# IPM_Schematic.net
KiCad netlist of a schematic drawn in Altium Designer
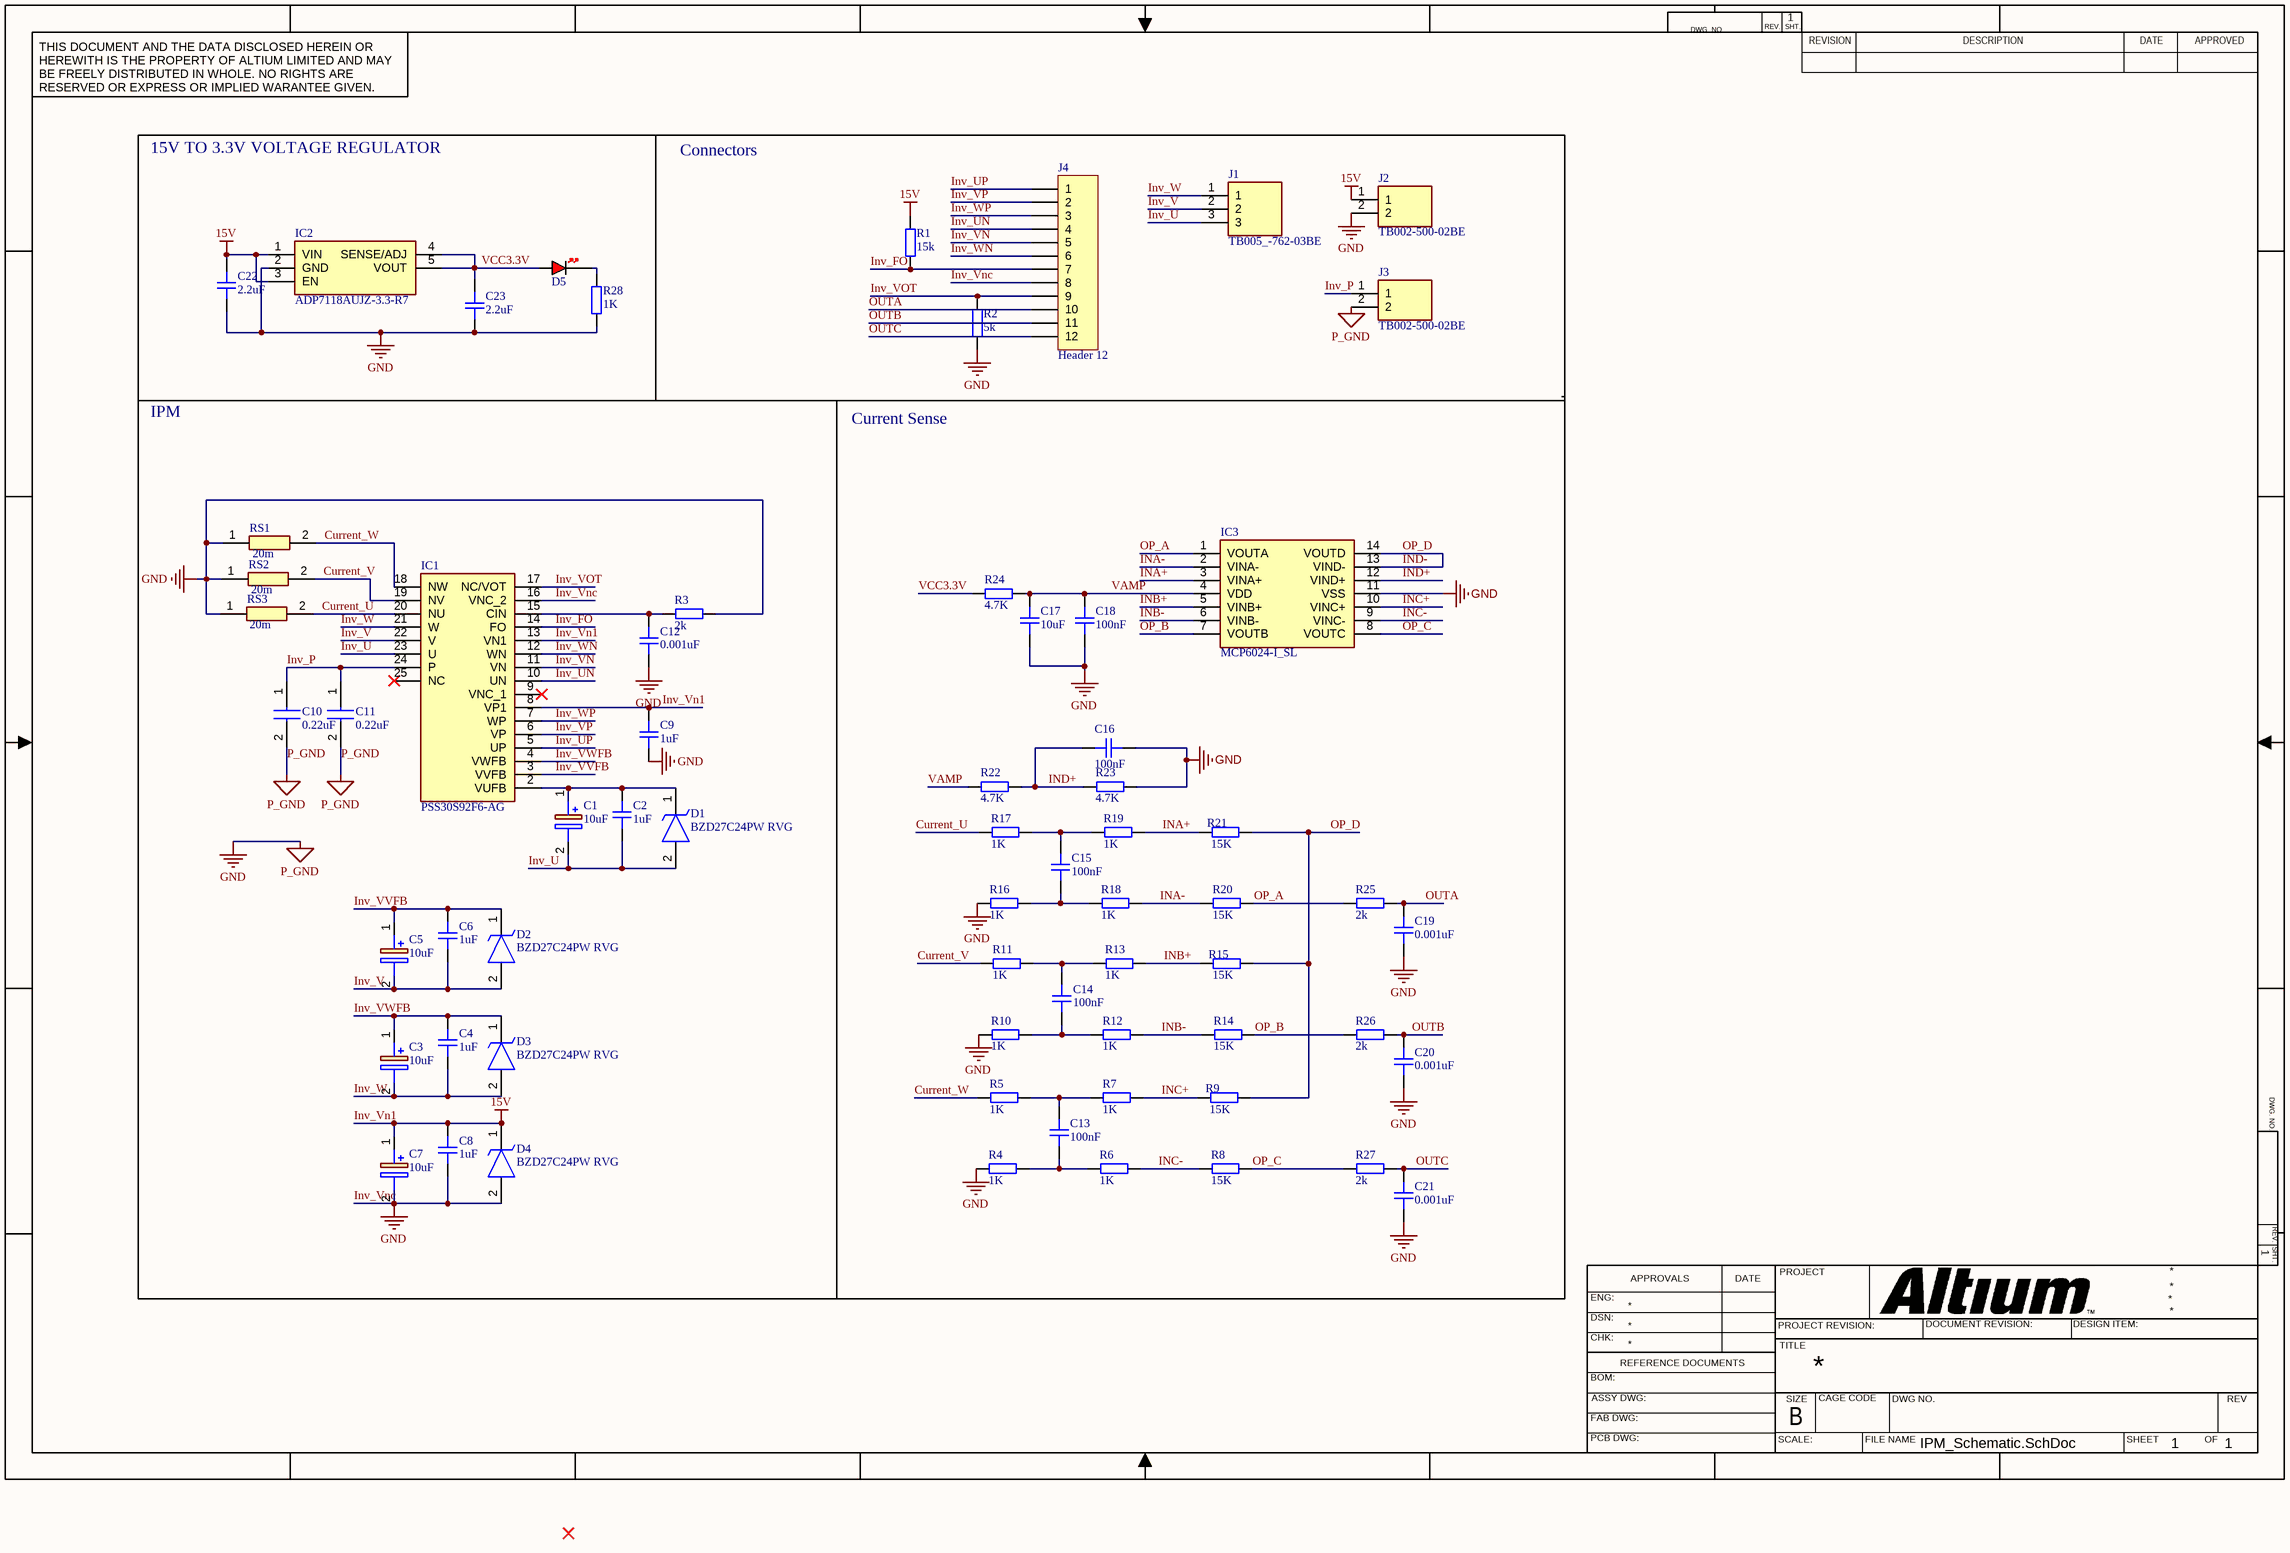
[diagram p0: IPM_Schematic.SchDoc]

(export (version "E")
  (design (tool "Eeschema 10.0.6"))
  (components
    (comp (ref "C1")
      (value "10uF")
      (footprint "SamacSys:EEE1AA220WR")
      (description "Capacitor Polarised")
      (fields
        (field (name "MANUFACTURER_PART_NUMBER") "EEE-FTH100UAR")
        (field (name "MOUSER PART NUMBER") "667-EEE-FTH100UAR")
      )
      (libsource (lib "*") (part "EEE-FTH100UAR"))
    )
    (comp (ref "C2")
      (value "1uF")
      (footprint "CAP_1206")
      (description "Capacitor SMD 1206 50V")
      (libsource (lib "Schematic-Lib-PhilsLab") (part "CAP_1206_50V"))
    )
    (comp (ref "C3")
      (value "10uF")
      (footprint "SamacSys:EEE1AA220WR")
      (description "Capacitor Polarised")
      (fields
        (field (name "MANUFACTURER_PART_NUMBER") "EEE-FTH100UAR")
        (field (name "MOUSER PART NUMBER") "667-EEE-FTH100UAR")
      )
      (libsource (lib "*") (part "EEE-FTH100UAR"))
    )
    (comp (ref "C4")
      (value "1uF")
      (footprint "CAP_1206")
      (description "Capacitor SMD 1206 50V")
      (libsource (lib "Schematic-Lib-PhilsLab") (part "CAP_1206_50V"))
    )
    (comp (ref "C5")
      (value "10uF")
      (footprint "SamacSys:EEE1AA220WR")
      (description "Capacitor Polarised")
      (fields
        (field (name "MANUFACTURER_PART_NUMBER") "EEE-FTH100UAR")
        (field (name "MOUSER PART NUMBER") "667-EEE-FTH100UAR")
      )
      (libsource (lib "*") (part "EEE-FTH100UAR"))
    )
    (comp (ref "C6")
      (value "1uF")
      (footprint "CAP_1206")
      (description "Capacitor SMD 1206 50V")
      (libsource (lib "Schematic-Lib-PhilsLab") (part "CAP_1206_50V"))
    )
    (comp (ref "C7")
      (value "10uF")
      (footprint "SamacSys:EEE1AA220WR")
      (description "Capacitor Polarised")
      (fields
        (field (name "MANUFACTURER_PART_NUMBER") "EEE-FTH100UAR")
        (field (name "MOUSER PART NUMBER") "667-EEE-FTH100UAR")
      )
      (libsource (lib "*") (part "EEE-FTH100UAR"))
    )
    (comp (ref "C8")
      (value "1uF")
      (footprint "CAP_1206")
      (description "Capacitor SMD 1206 50V")
      (libsource (lib "Schematic-Lib-PhilsLab") (part "CAP_1206_50V"))
    )
    (comp (ref "C9")
      (value "1uF")
      (footprint "CAP_1206")
      (description "Capacitor SMD 1206 50V")
      (libsource (lib "Schematic-Lib-PhilsLab") (part "CAP_1206_50V"))
    )
    (comp (ref "C10")
      (value "0.22uF")
      (footprint "SamacSys:CAPC5750X450N")
      (description "Capacitor")
      (fields
        (field (name "MANUFACTURER_PART_NUMBER") "2220Y1K20224KXTWS3")
        (field (name "MOUSER PART NUMBER") "843-2220Y1K20224KXTW")
      )
      (libsource (lib "*") (part "2220Y1K20224KXTWS3"))
    )
    (comp (ref "C11")
      (value "0.22uF")
      (footprint "SamacSys:CAPC5750X450N")
      (description "Capacitor")
      (fields
        (field (name "MANUFACTURER_PART_NUMBER") "2220Y1K20224KXTWS3")
        (field (name "MOUSER PART NUMBER") "843-2220Y1K20224KXTW")
      )
      (libsource (lib "*") (part "2220Y1K20224KXTWS3"))
    )
    (comp (ref "C12")
      (value "0.001uF")
      (footprint "CAP_0805")
      (description "Capacitor SMD 0805 25V")
      (libsource (lib "Schematic-Lib-PhilsLab") (part "CAP_0805_25V"))
    )
    (comp (ref "C13")
      (value "100nF")
      (footprint "CAP_0603")
      (description "Capacitor SMD 0603 50V")
      (libsource (lib "Schematic-Lib-PhilsLab") (part "CAP_0603_50V"))
    )
    (comp (ref "C14")
      (value "100nF")
      (footprint "CAP_0603")
      (description "Capacitor SMD 0603 50V")
      (libsource (lib "Schematic-Lib-PhilsLab") (part "CAP_0603_50V"))
    )
    (comp (ref "C15")
      (value "100nF")
      (footprint "CAP_0603")
      (description "Capacitor SMD 0603 50V")
      (libsource (lib "Schematic-Lib-PhilsLab") (part "CAP_0603_50V"))
    )
    (comp (ref "C16")
      (value "100nF")
      (footprint "CAP_0603")
      (description "Capacitor SMD 0603 50V")
      (libsource (lib "Schematic-Lib-PhilsLab") (part "CAP_0603_50V"))
    )
    (comp (ref "C17")
      (value "10uF")
      (footprint "CAP_0603")
      (description "Capacitor SMD 0603 50V")
      (libsource (lib "Schematic-Lib-PhilsLab") (part "CAP_0603_50V"))
    )
    (comp (ref "C18")
      (value "100nF")
      (footprint "CAP_0603")
      (description "Capacitor SMD 0603 50V")
      (libsource (lib "Schematic-Lib-PhilsLab") (part "CAP_0603_50V"))
    )
    (comp (ref "C19")
      (value "0.001uF")
      (footprint "CAP_0805")
      (description "Capacitor SMD 0805 25V")
      (libsource (lib "Schematic-Lib-PhilsLab") (part "CAP_0805_25V"))
    )
    (comp (ref "C20")
      (value "0.001uF")
      (footprint "CAP_0805")
      (description "Capacitor SMD 0805 25V")
      (libsource (lib "Schematic-Lib-PhilsLab") (part "CAP_0805_25V"))
    )
    (comp (ref "C21")
      (value "0.001uF")
      (footprint "CAP_0805")
      (description "Capacitor SMD 0805 25V")
      (libsource (lib "Schematic-Lib-PhilsLab") (part "CAP_0805_25V"))
    )
    (comp (ref "C22")
      (value "2.2uF")
      (footprint "CAP_0603")
      (description "Capacitor SMD 0603 50V")
      (libsource (lib "Schematic-Lib-PhilsLab") (part "CAP_0603_50V"))
    )
    (comp (ref "C23")
      (value "2.2uF")
      (footprint "CAP_0603")
      (description "Capacitor SMD 0603 50V")
      (libsource (lib "Schematic-Lib-PhilsLab") (part "CAP_0603_50V"))
    )
    (comp (ref "D1")
      (value "BZD27C24PW RVG")
      (footprint "SamacSys:SODFL3718X140N")
      (description "TVS Diode (Uni-directional)")
      (fields
        (field (name "MANUFACTURER_PART_NUMBER") "SJD12A28L01")
        (field (name "MOUSER PART NUMBER") "603-SJD12A28L01")
      )
      (libsource (lib "*") (part "SJD12A28L01"))
    )
    (comp (ref "D2")
      (value "BZD27C24PW RVG")
      (footprint "SamacSys:SODFL3718X140N")
      (description "TVS Diode (Uni-directional)")
      (fields
        (field (name "MANUFACTURER_PART_NUMBER") "SJD12A28L01")
        (field (name "MOUSER PART NUMBER") "603-SJD12A28L01")
      )
      (libsource (lib "*") (part "SJD12A28L01"))
    )
    (comp (ref "D3")
      (value "BZD27C24PW RVG")
      (footprint "SamacSys:SODFL3718X140N")
      (description "TVS Diode (Uni-directional)")
      (fields
        (field (name "MANUFACTURER_PART_NUMBER") "SJD12A28L01")
        (field (name "MOUSER PART NUMBER") "603-SJD12A28L01")
      )
      (libsource (lib "*") (part "SJD12A28L01"))
    )
    (comp (ref "D4")
      (value "BZD27C24PW RVG")
      (footprint "SamacSys:SODFL3718X140N")
      (description "TVS Diode (Uni-directional)")
      (fields
        (field (name "MANUFACTURER_PART_NUMBER") "SJD12A28L01")
        (field (name "MOUSER PART NUMBER") "603-SJD12A28L01")
      )
      (libsource (lib "*") (part "SJD12A28L01"))
    )
    (comp (ref "D5")
      (value "RED")
      (footprint "LED_0402_RED")
      (description "LED 0402 RED SMD")
      (libsource (lib "Schematic-Lib-PhilsLab") (part "LED_0402_RED"))
    )
    (comp (ref "IC1")
      (value "PSS30S92F6-AG")
      (footprint "SamacSys:PSS30S92F6AG")
      (description "Integrated Circuit")
      (fields (field (name "MOUSER PART NUMBER") "917-PSS30S92F6-AG"))
      (libsource (lib "*") (part "PSS30S92F6-AG"))
    )
    (comp (ref "IC2")
      (value "ADP7118AUJZ-3.3-R7")
      (footprint "SamacSys:SOT95P280X100-5N")
      (description "Integrated Circuit")
      (fields (field (name "MOUSER PART NUMBER") "584-ADP7118AUJZ3.3R7"))
      (libsource (lib "*") (part "ADP7118AUJZ-3.3-R7"))
    )
    (comp (ref "IC3")
      (value "MCP6024-I_SL")
      (footprint "SamacSys:SOIC127P600X175-14N")
      (description "Integrated Circuit")
      (fields
        (field (name "MANUFACTURER_PART_NUMBER") "MCP6024-I/SL")
        (field (name "MOUSER PART NUMBER") "579-MCP6024-I/SL")
      )
      (libsource (lib "*") (part "MCP6024-I_SL"))
    )
    (comp (ref "J1")
      (value "TB005_-762-03BE")
      (footprint "CUI_TB005 -762-03BE")
      (description "3 Position Wire to Board Terminal Block Horizontal with Board 0.300 (7.62mm) Through Hole")
      (fields (field (name "MF") "CUI") (field (name "MP") "TB005 -762-03BE"))
      (libsource (lib "TB005_-762-03BE") (part "TB005_-762-03BE"))
    )
    (comp (ref "J2")
      (value "TB002-500-02BE")
      (footprint "SamacSys:TB00250002BE")
      (description "Connector")
      (fields (field (name "MOUSER PART NUMBER") "490-TB002-500-02BE"))
      (libsource (lib "*") (part "TB002-500-02BE"))
    )
    (comp (ref "J3")
      (value "TB002-500-02BE")
      (footprint "SamacSys:TB00250002BE")
      (description "Connector")
      (fields (field (name "MOUSER PART NUMBER") "490-TB002-500-02BE"))
      (libsource (lib "*") (part "TB002-500-02BE"))
    )
    (comp (ref "J4")
      (value "Header 12")
      (footprint "HDR1X12")
      (description "Header, 12-Pin")
      (fields (field (name "PUBLISHER") "Altium Limited"))
      (libsource (lib "Miscellaneous Connectors") (part "Header 12"))
    )
    (comp (ref "R1")
      (value "15k")
      (footprint "RES_0603")
      (description "Resistor SMD 0603")
      (libsource (lib "Schematic-Lib-PhilsLab") (part "RES_0603"))
    )
    (comp (ref "R2")
      (value "5k")
      (footprint "RES_0603")
      (description "Resistor SMD 0603")
      (libsource (lib "Schematic-Lib-PhilsLab") (part "RES_0603"))
    )
    (comp (ref "R3")
      (value "2k")
      (footprint "RES_0805")
      (description "Resistor SMD 0805")
      (libsource (lib "Schematic-Lib-PhilsLab") (part "RES_0805"))
    )
    (comp (ref "R4")
      (value "1K")
      (footprint "RES_0603")
      (description "Resistor SMD 0603")
      (libsource (lib "Schematic-Lib-PhilsLab") (part "RES_0603"))
    )
    (comp (ref "R5")
      (value "1K")
      (footprint "RES_0603")
      (description "Resistor SMD 0603")
      (libsource (lib "Schematic-Lib-PhilsLab") (part "RES_0603"))
    )
    (comp (ref "R6")
      (value "1K")
      (footprint "RES_0603")
      (description "Resistor SMD 0603")
      (libsource (lib "Schematic-Lib-PhilsLab") (part "RES_0603"))
    )
    (comp (ref "R7")
      (value "1K")
      (footprint "RES_0603")
      (description "Resistor SMD 0603")
      (libsource (lib "Schematic-Lib-PhilsLab") (part "RES_0603"))
    )
    (comp (ref "R8")
      (value "15K")
      (footprint "RES_0603")
      (description "Resistor SMD 0603")
      (libsource (lib "Schematic-Lib-PhilsLab") (part "RES_0603"))
    )
    (comp (ref "R9")
      (value "15K")
      (footprint "RES_0603")
      (description "Resistor SMD 0603")
      (libsource (lib "Schematic-Lib-PhilsLab") (part "RES_0603"))
    )
    (comp (ref "R10")
      (value "1K")
      (footprint "RES_0603")
      (description "Resistor SMD 0603")
      (libsource (lib "Schematic-Lib-PhilsLab") (part "RES_0603"))
    )
    (comp (ref "R11")
      (value "1K")
      (footprint "RES_0603")
      (description "Resistor SMD 0603")
      (libsource (lib "Schematic-Lib-PhilsLab") (part "RES_0603"))
    )
    (comp (ref "R12")
      (value "1K")
      (footprint "RES_0603")
      (description "Resistor SMD 0603")
      (libsource (lib "Schematic-Lib-PhilsLab") (part "RES_0603"))
    )
    (comp (ref "R13")
      (value "1K")
      (footprint "RES_0603")
      (description "Resistor SMD 0603")
      (libsource (lib "Schematic-Lib-PhilsLab") (part "RES_0603"))
    )
    (comp (ref "R14")
      (value "15K")
      (footprint "RES_0603")
      (description "Resistor SMD 0603")
      (libsource (lib "Schematic-Lib-PhilsLab") (part "RES_0603"))
    )
    (comp (ref "R15")
      (value "15K")
      (footprint "RES_0603")
      (description "Resistor SMD 0603")
      (libsource (lib "Schematic-Lib-PhilsLab") (part "RES_0603"))
    )
    (comp (ref "R16")
      (value "1K")
      (footprint "RES_0603")
      (description "Resistor SMD 0603")
      (libsource (lib "Schematic-Lib-PhilsLab") (part "RES_0603"))
    )
    (comp (ref "R17")
      (value "1K")
      (footprint "RES_0603")
      (description "Resistor SMD 0603")
      (libsource (lib "Schematic-Lib-PhilsLab") (part "RES_0603"))
    )
    (comp (ref "R18")
      (value "1K")
      (footprint "RES_0603")
      (description "Resistor SMD 0603")
      (libsource (lib "Schematic-Lib-PhilsLab") (part "RES_0603"))
    )
    (comp (ref "R19")
      (value "1K")
      (footprint "RES_0603")
      (description "Resistor SMD 0603")
      (libsource (lib "Schematic-Lib-PhilsLab") (part "RES_0603"))
    )
    (comp (ref "R20")
      (value "15K")
      (footprint "RES_0603")
      (description "Resistor SMD 0603")
      (libsource (lib "Schematic-Lib-PhilsLab") (part "RES_0603"))
    )
    (comp (ref "R21")
      (value "15K")
      (footprint "RES_0603")
      (description "Resistor SMD 0603")
      (libsource (lib "Schematic-Lib-PhilsLab") (part "RES_0603"))
    )
    (comp (ref "R22")
      (value "4.7K")
      (footprint "RES_0603")
      (description "Resistor SMD 0603")
      (libsource (lib "Schematic-Lib-PhilsLab") (part "RES_0603"))
    )
    (comp (ref "R23")
      (value "4.7K")
      (footprint "RES_0603")
      (description "Resistor SMD 0603")
      (libsource (lib "Schematic-Lib-PhilsLab") (part "RES_0603"))
    )
    (comp (ref "R24")
      (value "4.7K")
      (footprint "RES_0603")
      (description "Resistor SMD 0603")
      (libsource (lib "Schematic-Lib-PhilsLab") (part "RES_0603"))
    )
    (comp (ref "R25")
      (value "2k")
      (footprint "RES_0805")
      (description "Resistor SMD 0805")
      (libsource (lib "Schematic-Lib-PhilsLab") (part "RES_0805"))
    )
    (comp (ref "R26")
      (value "2k")
      (footprint "RES_0805")
      (description "Resistor SMD 0805")
      (libsource (lib "Schematic-Lib-PhilsLab") (part "RES_0805"))
    )
    (comp (ref "R27")
      (value "2k")
      (footprint "RES_0805")
      (description "Resistor SMD 0805")
      (libsource (lib "Schematic-Lib-PhilsLab") (part "RES_0805"))
    )
    (comp (ref "R28")
      (value "1K")
      (footprint "RES_0402")
      (description "Resistor SMD 0402")
      (libsource (lib "Schematic-Lib-PhilsLab") (part "RES_0402"))
    )
    (comp (ref "RS1")
      (value "20m")
      (footprint "SamacSys:RESC6432X89N")
      (description "Resistor")
      (fields
        (field (name "MANUFACTURER_PART_NUMBER") "PE2512FKE7W0R02L")
        (field (name "MOUSER PART NUMBER") "603-PE2512FKE7W0R02L")
      )
      (libsource (lib "*") (part "PE2512FKE7W0R02L"))
    )
    (comp (ref "RS2")
      (value "20m")
      (footprint "SamacSys:RESC6432X89N")
      (description "Resistor")
      (fields
        (field (name "MANUFACTURER_PART_NUMBER") "PE2512FKE7W0R02L")
        (field (name "MOUSER PART NUMBER") "603-PE2512FKE7W0R02L")
      )
      (libsource (lib "*") (part "PE2512FKE7W0R02L"))
    )
    (comp (ref "RS3")
      (value "20m")
      (footprint "SamacSys:RESC6432X89N")
      (description "Resistor")
      (fields
        (field (name "MANUFACTURER_PART_NUMBER") "PE2512FKE7W0R02L")
        (field (name "MOUSER PART NUMBER") "603-PE2512FKE7W0R02L")
      )
      (libsource (lib "*") (part "PE2512FKE7W0R02L"))
    )
  )
  (nets
    (net (code "1") (name "/Current_U") (class "Default")
      (node (ref "IC1") (pin "20") (pinfunction "NU_20") (pintype "passive"))
      (node (ref "R17") (pin "1") (pinfunction "1_1") (pintype "passive"))
      (node (ref "RS3") (pin "2") (pinfunction "2_2") (pintype "passive"))
    )
    (net (code "2") (name "/Current_V") (class "Default")
      (node (ref "IC1") (pin "19") (pinfunction "NV_19") (pintype "passive"))
      (node (ref "R11") (pin "1") (pinfunction "1_1") (pintype "passive"))
      (node (ref "RS2") (pin "2") (pinfunction "2_2") (pintype "passive"))
    )
    (net (code "3") (name "/Current_W") (class "Default")
      (node (ref "IC1") (pin "18") (pinfunction "NW_18") (pintype "passive"))
      (node (ref "R5") (pin "1") (pinfunction "1_1") (pintype "passive"))
      (node (ref "RS1") (pin "2") (pinfunction "2_2") (pintype "passive"))
    )
    (net (code "4") (name "/INA+") (class "Default")
      (node (ref "IC3") (pin "3") (pinfunction "VINA+_3") (pintype "passive"))
      (node (ref "R19") (pin "2") (pinfunction "2_2") (pintype "passive"))
      (node (ref "R21") (pin "1") (pinfunction "1_1") (pintype "passive"))
    )
    (net (code "5") (name "/INA-") (class "Default")
      (node (ref "IC3") (pin "2") (pinfunction "VINA-_2") (pintype "passive"))
      (node (ref "R18") (pin "2") (pinfunction "2_2") (pintype "passive"))
      (node (ref "R20") (pin "1") (pinfunction "1_1") (pintype "passive"))
    )
    (net (code "6") (name "/INB+") (class "Default")
      (node (ref "IC3") (pin "5") (pinfunction "VINB+_5") (pintype "passive"))
      (node (ref "R13") (pin "2") (pinfunction "2_2") (pintype "passive"))
      (node (ref "R15") (pin "1") (pinfunction "1_1") (pintype "passive"))
    )
    (net (code "7") (name "/INB-") (class "Default")
      (node (ref "IC3") (pin "6") (pinfunction "VINB-_6") (pintype "passive"))
      (node (ref "R12") (pin "2") (pinfunction "2_2") (pintype "passive"))
      (node (ref "R14") (pin "1") (pinfunction "1_1") (pintype "passive"))
    )
    (net (code "8") (name "/INC+") (class "Default")
      (node (ref "IC3") (pin "10") (pinfunction "VINC+_10") (pintype "passive"))
      (node (ref "R7") (pin "2") (pinfunction "2_2") (pintype "passive"))
      (node (ref "R9") (pin "1") (pinfunction "1_1") (pintype "passive"))
    )
    (net (code "9") (name "/INC-") (class "Default")
      (node (ref "IC3") (pin "9") (pinfunction "VINC-_9") (pintype "passive"))
      (node (ref "R6") (pin "2") (pinfunction "2_2") (pintype "passive"))
      (node (ref "R8") (pin "1") (pinfunction "1_1") (pintype "passive"))
    )
    (net (code "10") (name "/IND+") (class "Default")
      (node (ref "C16") (pin "2") (pinfunction "2_2") (pintype "passive"))
      (node (ref "IC3") (pin "12") (pinfunction "VIND+_12") (pintype "passive"))
      (node (ref "R22") (pin "2") (pinfunction "2_2") (pintype "passive"))
      (node (ref "R23") (pin "1") (pinfunction "1_1") (pintype "passive"))
    )
    (net (code "11") (name "/IND-") (class "Default")
      (node (ref "IC3") (pin "13") (pinfunction "VIND-_13") (pintype "passive"))
      (node (ref "IC3") (pin "14") (pinfunction "VOUTD_14") (pintype "passive"))
      (node (ref "R15") (pin "2") (pinfunction "2_2") (pintype "passive"))
      (node (ref "R21") (pin "2") (pinfunction "2_2") (pintype "passive"))
      (node (ref "R9") (pin "2") (pinfunction "2_2") (pintype "passive"))
    )
    (net (code "12") (name "/Inv_FO") (class "Default")
      (node (ref "IC1") (pin "14") (pinfunction "FO_14") (pintype "passive"))
      (node (ref "J4") (pin "7") (pinfunction "7_7") (pintype "passive"))
      (node (ref "R1") (pin "1") (pinfunction "1_1") (pintype "passive"))
    )
    (net (code "13") (name "/Inv_P") (class "Default")
      (node (ref "C10") (pin "1") (pinfunction "1_1") (pintype "passive"))
      (node (ref "C11") (pin "1") (pinfunction "1_1") (pintype "passive"))
      (node (ref "IC1") (pin "24") (pinfunction "P_24") (pintype "passive"))
      (node (ref "J3") (pin "1") (pinfunction "1_1") (pintype "passive"))
    )
    (net (code "14") (name "/Inv_U") (class "Default")
      (node (ref "C1") (pin "2") (pinfunction "-_2") (pintype "passive"))
      (node (ref "C2") (pin "1") (pinfunction "1_1") (pintype "passive"))
      (node (ref "D1") (pin "2") (pinfunction "A_2") (pintype "passive"))
      (node (ref "IC1") (pin "23") (pinfunction "U_23") (pintype "passive"))
      (node (ref "J1") (pin "3") (pinfunction "3_3") (pintype "passive"))
    )
    (net (code "15") (name "/Inv_UN") (class "Default")
      (node (ref "IC1") (pin "10") (pinfunction "UN_10") (pintype "passive"))
      (node (ref "J4") (pin "4") (pinfunction "4_4") (pintype "passive"))
    )
    (net (code "16") (name "/Inv_UP") (class "Default")
      (node (ref "IC1") (pin "5") (pinfunction "UP_5") (pintype "passive"))
      (node (ref "J4") (pin "1") (pinfunction "1_1") (pintype "passive"))
    )
    (net (code "17") (name "/Inv_V") (class "Default")
      (node (ref "C5") (pin "2") (pinfunction "-_2") (pintype "passive"))
      (node (ref "C6") (pin "1") (pinfunction "1_1") (pintype "passive"))
      (node (ref "D2") (pin "2") (pinfunction "A_2") (pintype "passive"))
      (node (ref "IC1") (pin "22") (pinfunction "V_22") (pintype "passive"))
      (node (ref "J1") (pin "2") (pinfunction "2_2") (pintype "passive"))
    )
    (net (code "18") (name "/Inv_VN") (class "Default")
      (node (ref "IC1") (pin "11") (pinfunction "VN_11") (pintype "passive"))
      (node (ref "J4") (pin "5") (pinfunction "5_5") (pintype "passive"))
    )
    (net (code "19") (name "/Inv_VOT") (class "Default")
      (node (ref "IC1") (pin "17") (pinfunction "NC/VOT_17") (pintype "passive"))
      (node (ref "J4") (pin "9") (pinfunction "9_9") (pintype "passive"))
      (node (ref "R2") (pin "2") (pinfunction "2_2") (pintype "passive"))
    )
    (net (code "20") (name "/Inv_VP") (class "Default")
      (node (ref "IC1") (pin "6") (pinfunction "VP_6") (pintype "passive"))
      (node (ref "J4") (pin "2") (pinfunction "2_2") (pintype "passive"))
    )
    (net (code "21") (name "/Inv_VVFB") (class "Default")
      (node (ref "C5") (pin "1") (pinfunction "+_1") (pintype "passive"))
      (node (ref "C6") (pin "2") (pinfunction "2_2") (pintype "passive"))
      (node (ref "D2") (pin "1") (pinfunction "K_1") (pintype "passive"))
      (node (ref "IC1") (pin "3") (pinfunction "VVFB_3") (pintype "passive"))
    )
    (net (code "22") (name "/Inv_VWFB") (class "Default")
      (node (ref "C3") (pin "1") (pinfunction "+_1") (pintype "passive"))
      (node (ref "C4") (pin "2") (pinfunction "2_2") (pintype "passive"))
      (node (ref "D3") (pin "1") (pinfunction "K_1") (pintype "passive"))
      (node (ref "IC1") (pin "4") (pinfunction "VWFB_4") (pintype "passive"))
    )
    (net (code "23") (name "/Inv_W") (class "Default")
      (node (ref "C3") (pin "2") (pinfunction "-_2") (pintype "passive"))
      (node (ref "C4") (pin "1") (pinfunction "1_1") (pintype "passive"))
      (node (ref "D3") (pin "2") (pinfunction "A_2") (pintype "passive"))
      (node (ref "IC1") (pin "21") (pinfunction "W_21") (pintype "passive"))
      (node (ref "J1") (pin "1") (pinfunction "1_1") (pintype "passive"))
    )
    (net (code "24") (name "/Inv_WN") (class "Default")
      (node (ref "IC1") (pin "12") (pinfunction "WN_12") (pintype "passive"))
      (node (ref "J4") (pin "6") (pinfunction "6_6") (pintype "passive"))
    )
    (net (code "25") (name "/Inv_WP") (class "Default")
      (node (ref "IC1") (pin "7") (pinfunction "WP_7") (pintype "passive"))
      (node (ref "J4") (pin "3") (pinfunction "3_3") (pintype "passive"))
    )
    (net (code "26") (name "/OP_A") (class "Default")
      (node (ref "IC3") (pin "1") (pinfunction "VOUTA_1") (pintype "passive"))
      (node (ref "R20") (pin "2") (pinfunction "2_2") (pintype "passive"))
      (node (ref "R25") (pin "1") (pinfunction "1_1") (pintype "passive"))
    )
    (net (code "27") (name "/OP_B") (class "Default")
      (node (ref "IC3") (pin "7") (pinfunction "VOUTB_7") (pintype "passive"))
      (node (ref "R14") (pin "2") (pinfunction "2_2") (pintype "passive"))
      (node (ref "R26") (pin "1") (pinfunction "1_1") (pintype "passive"))
    )
    (net (code "28") (name "/OP_C") (class "Default")
      (node (ref "IC3") (pin "8") (pinfunction "VOUTC_8") (pintype "passive"))
      (node (ref "R27") (pin "1") (pinfunction "1_1") (pintype "passive"))
      (node (ref "R8") (pin "2") (pinfunction "2_2") (pintype "passive"))
    )
    (net (code "29") (name "/OUTA") (class "Default")
      (node (ref "C19") (pin "1") (pinfunction "1_1") (pintype "passive"))
      (node (ref "J4") (pin "10") (pinfunction "10_10") (pintype "passive"))
      (node (ref "R25") (pin "2") (pinfunction "2_2") (pintype "passive"))
    )
    (net (code "30") (name "/OUTB") (class "Default")
      (node (ref "C20") (pin "1") (pinfunction "1_1") (pintype "passive"))
      (node (ref "J4") (pin "11") (pinfunction "11_11") (pintype "passive"))
      (node (ref "R26") (pin "2") (pinfunction "2_2") (pintype "passive"))
    )
    (net (code "31") (name "/OUTC") (class "Default")
      (node (ref "C21") (pin "1") (pinfunction "1_1") (pintype "passive"))
      (node (ref "J4") (pin "12") (pinfunction "12_12") (pintype "passive"))
      (node (ref "R27") (pin "2") (pinfunction "2_2") (pintype "passive"))
    )
    (net (code "32") (name "/VAMP") (class "Default")
      (node (ref "C17") (pin "1") (pinfunction "1_1") (pintype "passive"))
      (node (ref "C18") (pin "1") (pinfunction "1_1") (pintype "passive"))
      (node (ref "IC3") (pin "4") (pinfunction "VDD_4") (pintype "passive"))
      (node (ref "R22") (pin "1") (pinfunction "1_1") (pintype "passive"))
      (node (ref "R24") (pin "2") (pinfunction "2_2") (pintype "passive"))
    )
    (net (code "33") (name "/VCC3.3V") (class "Default")
      (node (ref "C23") (pin "2") (pinfunction "2_2") (pintype "passive"))
      (node (ref "D5") (pin "A") (pinfunction "A_A") (pintype "passive"))
      (node (ref "IC2") (pin "4") (pinfunction "SENSE/ADJ_4") (pintype "passive"))
      (node (ref "IC2") (pin "5") (pinfunction "VOUT_5") (pintype "passive"))
      (node (ref "R24") (pin "1") (pinfunction "1_1") (pintype "passive"))
    )
    (net (code "34") (name "15V") (class "Default")
      (node (ref "C22") (pin "2") (pinfunction "2_2") (pintype "passive"))
      (node (ref "C7") (pin "1") (pinfunction "+_1") (pintype "passive"))
      (node (ref "C8") (pin "2") (pinfunction "2_2") (pintype "passive"))
      (node (ref "C9") (pin "2") (pinfunction "2_2") (pintype "passive"))
      (node (ref "D4") (pin "1") (pinfunction "K_1") (pintype "passive"))
      (node (ref "IC1") (pin "13") (pinfunction "VN1_13") (pintype "passive"))
      (node (ref "IC1") (pin "8") (pinfunction "VP1_8") (pintype "passive"))
      (node (ref "IC2") (pin "1") (pinfunction "VIN_1") (pintype "passive"))
      (node (ref "IC2") (pin "3") (pinfunction "EN_3") (pintype "passive"))
      (node (ref "J2") (pin "1") (pinfunction "1_1") (pintype "passive"))
      (node (ref "R1") (pin "2") (pinfunction "2_2") (pintype "passive"))
    )
    (net (code "35") (name "GND") (class "Default")
      (node (ref "C10") (pin "2") (pinfunction "2_2") (pintype "passive"))
      (node (ref "C11") (pin "2") (pinfunction "2_2") (pintype "passive"))
      (node (ref "C12") (pin "2") (pinfunction "2_2") (pintype "passive"))
      (node (ref "C16") (pin "1") (pinfunction "1_1") (pintype "passive"))
      (node (ref "C17") (pin "2") (pinfunction "2_2") (pintype "passive"))
      (node (ref "C18") (pin "2") (pinfunction "2_2") (pintype "passive"))
      (node (ref "C19") (pin "2") (pinfunction "2_2") (pintype "passive"))
      (node (ref "C20") (pin "2") (pinfunction "2_2") (pintype "passive"))
      (node (ref "C21") (pin "2") (pinfunction "2_2") (pintype "passive"))
      (node (ref "C22") (pin "1") (pinfunction "1_1") (pintype "passive"))
      (node (ref "C23") (pin "1") (pinfunction "1_1") (pintype "passive"))
      (node (ref "C7") (pin "2") (pinfunction "-_2") (pintype "passive"))
      (node (ref "C8") (pin "1") (pinfunction "1_1") (pintype "passive"))
      (node (ref "C9") (pin "1") (pinfunction "1_1") (pintype "passive"))
      (node (ref "D4") (pin "2") (pinfunction "A_2") (pintype "passive"))
      (node (ref "IC1") (pin "16") (pinfunction "VNC_2_16") (pintype "passive"))
      (node (ref "IC2") (pin "2") (pinfunction "GND_2") (pintype "passive"))
      (node (ref "IC3") (pin "11") (pinfunction "VSS_11") (pintype "passive"))
      (node (ref "J2") (pin "2") (pinfunction "2_2") (pintype "passive"))
      (node (ref "J3") (pin "2") (pinfunction "2_2") (pintype "passive"))
      (node (ref "J4") (pin "8") (pinfunction "8_8") (pintype "passive"))
      (node (ref "R10") (pin "1") (pinfunction "1_1") (pintype "passive"))
      (node (ref "R16") (pin "1") (pinfunction "1_1") (pintype "passive"))
      (node (ref "R2") (pin "1") (pinfunction "1_1") (pintype "passive"))
      (node (ref "R23") (pin "2") (pinfunction "2_2") (pintype "passive"))
      (node (ref "R28") (pin "1") (pinfunction "1_1") (pintype "passive"))
      (node (ref "R3") (pin "2") (pinfunction "2_2") (pintype "passive"))
      (node (ref "R4") (pin "1") (pinfunction "1_1") (pintype "passive"))
      (node (ref "RS1") (pin "1") (pinfunction "1_1") (pintype "passive"))
      (node (ref "RS2") (pin "1") (pinfunction "1_1") (pintype "passive"))
      (node (ref "RS3") (pin "1") (pinfunction "1_1") (pintype "passive"))
    )
    (net (code "36") (name "Net-(C1-+)") (class "Default")
      (node (ref "C1") (pin "1") (pinfunction "+_1") (pintype "passive"))
      (node (ref "C2") (pin "2") (pinfunction "2_2") (pintype "passive"))
      (node (ref "D1") (pin "1") (pinfunction "K_1") (pintype "passive"))
      (node (ref "IC1") (pin "2") (pinfunction "VUFB_2") (pintype "passive"))
    )
    (net (code "37") (name "Net-(C13-Pad1)") (class "Default")
      (node (ref "C13") (pin "1") (pinfunction "1_1") (pintype "passive"))
      (node (ref "R4") (pin "2") (pinfunction "2_2") (pintype "passive"))
      (node (ref "R6") (pin "1") (pinfunction "1_1") (pintype "passive"))
    )
    (net (code "38") (name "Net-(C13-Pad2)") (class "Default")
      (node (ref "C13") (pin "2") (pinfunction "2_2") (pintype "passive"))
      (node (ref "R5") (pin "2") (pinfunction "2_2") (pintype "passive"))
      (node (ref "R7") (pin "1") (pinfunction "1_1") (pintype "passive"))
    )
    (net (code "39") (name "Net-(C14-Pad1)") (class "Default")
      (node (ref "C14") (pin "1") (pinfunction "1_1") (pintype "passive"))
      (node (ref "R10") (pin "2") (pinfunction "2_2") (pintype "passive"))
      (node (ref "R12") (pin "1") (pinfunction "1_1") (pintype "passive"))
    )
    (net (code "40") (name "Net-(C14-Pad2)") (class "Default")
      (node (ref "C14") (pin "2") (pinfunction "2_2") (pintype "passive"))
      (node (ref "R11") (pin "2") (pinfunction "2_2") (pintype "passive"))
      (node (ref "R13") (pin "1") (pinfunction "1_1") (pintype "passive"))
    )
    (net (code "41") (name "Net-(C15-Pad1)") (class "Default")
      (node (ref "C15") (pin "1") (pinfunction "1_1") (pintype "passive"))
      (node (ref "R16") (pin "2") (pinfunction "2_2") (pintype "passive"))
      (node (ref "R18") (pin "1") (pinfunction "1_1") (pintype "passive"))
    )
    (net (code "42") (name "Net-(C15-Pad2)") (class "Default")
      (node (ref "C15") (pin "2") (pinfunction "2_2") (pintype "passive"))
      (node (ref "R17") (pin "2") (pinfunction "2_2") (pintype "passive"))
      (node (ref "R19") (pin "1") (pinfunction "1_1") (pintype "passive"))
    )
    (net (code "43") (name "Net-(D5-PadK)") (class "Default")
      (node (ref "D5") (pin "K") (pinfunction "K_K") (pintype "passive"))
      (node (ref "R28") (pin "2") (pinfunction "2_2") (pintype "passive"))
    )
    (net (code "44") (name "Net-(IC1-CIN)") (class "Default")
      (node (ref "C12") (pin "1") (pinfunction "1_1") (pintype "passive"))
      (node (ref "IC1") (pin "15") (pinfunction "CIN_15") (pintype "passive"))
      (node (ref "R3") (pin "1") (pinfunction "1_1") (pintype "passive"))
    )
    (net (code "45") (name "unconnected-(IC1-NC-Pad25)") (class "Default")
      (node (ref "IC1") (pin "25") (pinfunction "NC_25") (pintype "passive+no_connect"))
    )
    (net (code "46") (name "unconnected-(IC1-VNC_1-Pad9)") (class "Default")
      (node (ref "IC1") (pin "9") (pinfunction "VNC_1_9") (pintype "passive+no_connect"))
    )
  )
)
